# 03_-_Arduino_pcb_Schematic.net
KiCad netlist of a schematic drawn in Altium Designer
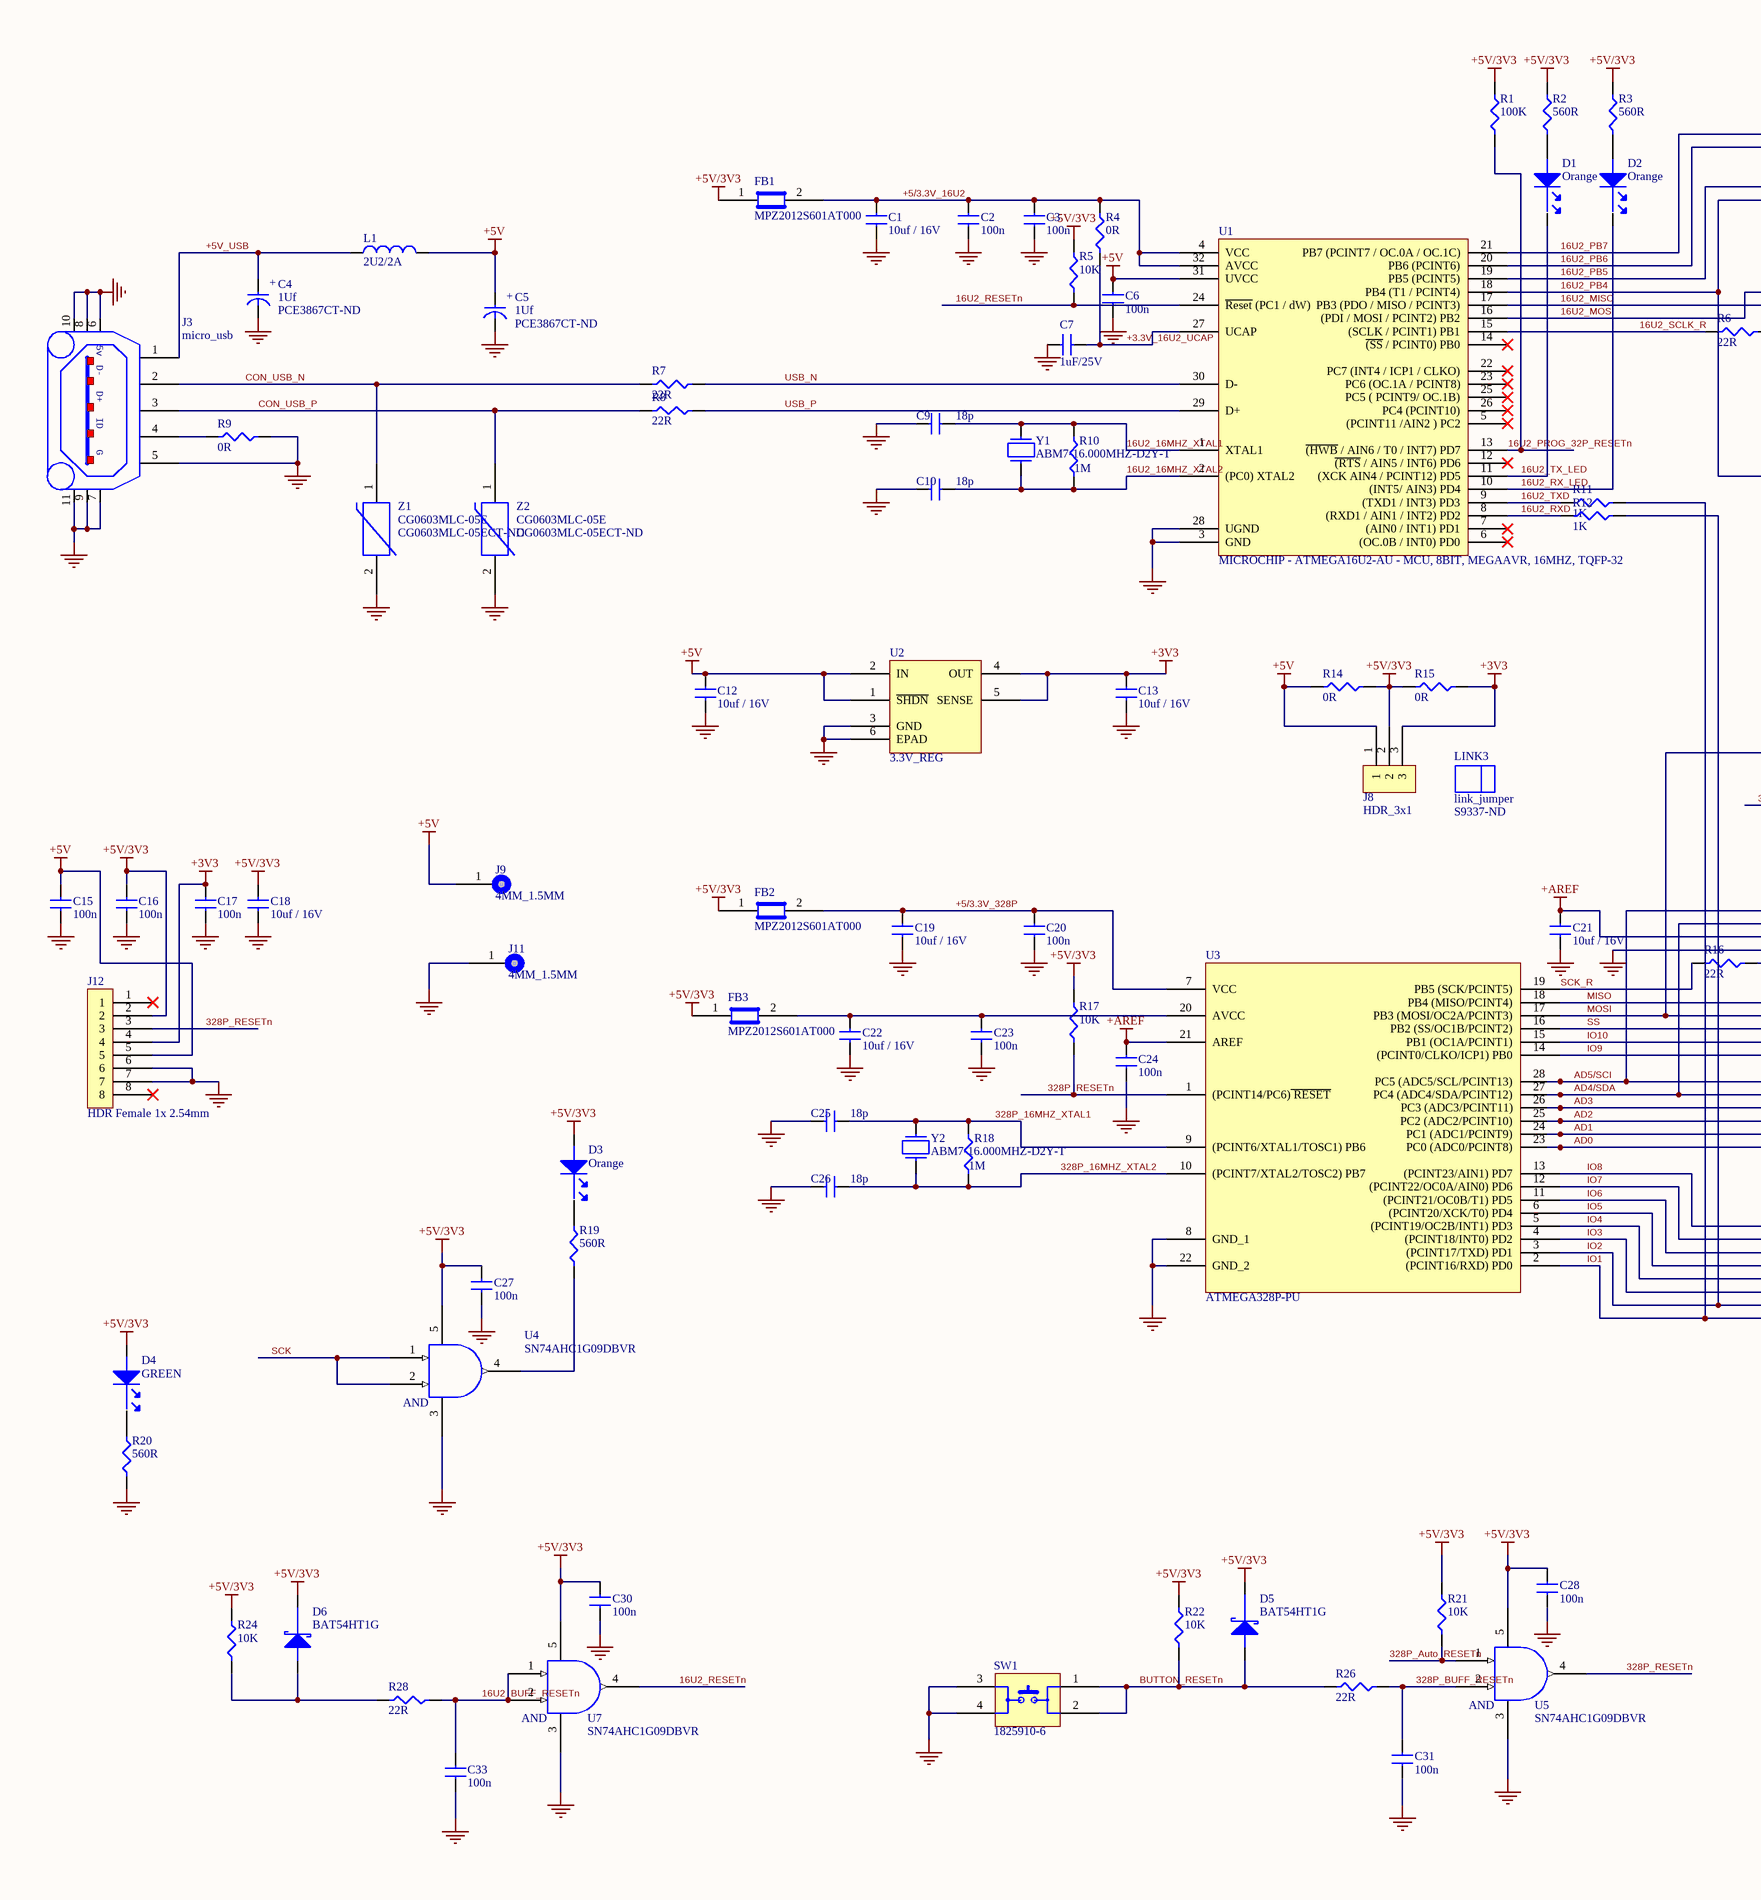
[diagram p0: [03] - Arduino_pcb_Schematic.SchDoc, left]
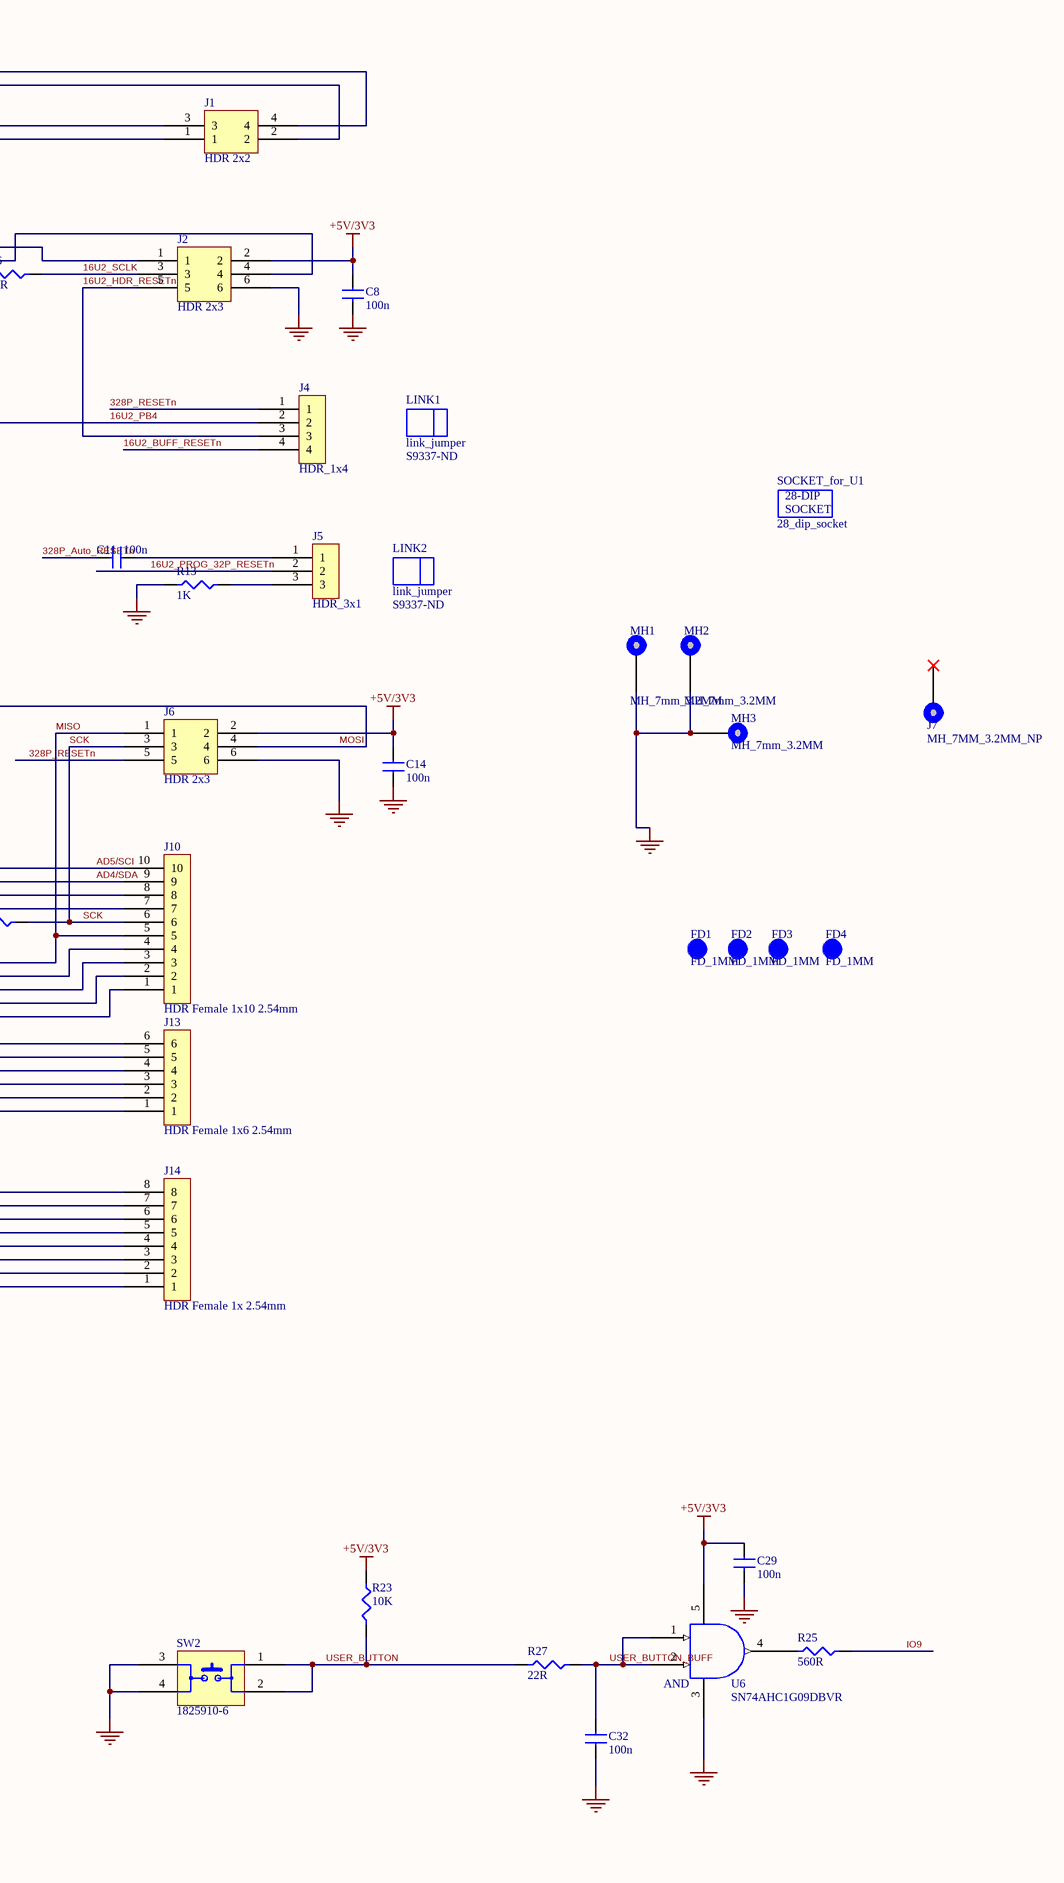
[diagram p1: [03] - Arduino_pcb_Schematic.SchDoc, right]

(export (version "E")
  (design (tool "Eeschema 10.0.6"))
  (components
    (comp (ref "C1")
      (value "10uf / 16V")
      (footprint "C0805_145")
      (fields
        (field (name "MANUFACTURER") "TDK")
        (field (name "MANUFACTURER PART NUMBER") "C2012X5R1C106K085AC")
        (field (name "TOLERANCE") "10%")
      )
      (libsource (lib "Arduino_pcb") (part "C2012X5R1C106K085AC"))
    )
    (comp (ref "C2")
      (value "100n")
      (footprint "C0805_95")
      (fields
        (field (name "MANUFACTURER") "TDK")
        (field (name "MANUFACTURER PART NUMBER") "C2012X7R1H104K085AA")
        (field (name "TOLERANCE") "10%")
      )
      (libsource (lib "Arduino_pcb") (part "C2012X7R1H104K085AA"))
    )
    (comp (ref "C3")
      (value "100n")
      (footprint "C0805_95")
      (fields
        (field (name "MANUFACTURER") "TDK")
        (field (name "MANUFACTURER PART NUMBER") "C2012X7R1H104K085AA")
        (field (name "TOLERANCE") "10%")
      )
      (libsource (lib "Arduino_pcb") (part "C2012X7R1H104K085AA"))
    )
    (comp (ref "C4")
      (value "1Uf")
      (footprint "C_ALIMUNUM_C_Size")
      (description "Cap Aluminum 100uF 10V 20% (5 X 5.4mm) SMD 50mA 1000 hr 85°C T/R")
      (fields
        (field (name "MANUFACTURER") "Panasonic")
        (field (name "MANUFACTURER PART NUMBER") "EEE-1AA101WR")
        (field (name "SUPPLIER PART NUMBER 1") "PCE3867CT-ND")
      )
      (libsource (lib "Arduino_pcb") (part "EEE-1AA101WR"))
    )
    (comp (ref "C5")
      (value "1Uf")
      (footprint "C_ALIMUNUM_C_Size")
      (description "Cap Aluminum 100uF 10V 20% (5 X 5.4mm) SMD 50mA 1000 hr 85°C T/R")
      (fields
        (field (name "MANUFACTURER") "Panasonic")
        (field (name "MANUFACTURER PART NUMBER") "EEE-1AA101WR")
        (field (name "SUPPLIER PART NUMBER 1") "PCE3867CT-ND")
      )
      (libsource (lib "Arduino_pcb") (part "EEE-1AA101WR"))
    )
    (comp (ref "C6")
      (value "100n")
      (footprint "C0805_95")
      (fields
        (field (name "MANUFACTURER") "TDK")
        (field (name "MANUFACTURER PART NUMBER") "C2012X7R1H104K085AA")
        (field (name "TOLERANCE") "10%")
      )
      (libsource (lib "Arduino_pcb") (part "C2012X7R1H104K085AA"))
    )
    (comp (ref "C7")
      (value "1uF/25V")
      (footprint "C0805_145")
      (fields
        (field (name "MANUFACTURER") "TDK")
        (field (name "MANUFACTURER PART NUMBER") "C2012X5R1E105K125AA")
        (field (name "TOLERANCE") "10%")
      )
      (libsource (lib "Arduino_pcb") (part "C2012X5R1E105K125AA"))
    )
    (comp (ref "C8")
      (value "100n")
      (footprint "C0805_95")
      (fields
        (field (name "MANUFACTURER") "TDK")
        (field (name "MANUFACTURER PART NUMBER") "C2012X7R1H104K085AA")
        (field (name "TOLERANCE") "10%")
      )
      (libsource (lib "Arduino_pcb") (part "C2012X7R1H104K085AA"))
    )
    (comp (ref "C9")
      (value "18p")
      (footprint "C0805_95")
      (description "CAP CER 18PF 50V C0G/NP0 0805")
      (fields
        (field (name "MANUFACTURER") "KEMET")
        (field (name "MANUFACTURER PART NUMBER") "C0805C180J5GACTU")
      )
      (libsource (lib "Arduino_pcb") (part "C0805C180J5GACTU"))
    )
    (comp (ref "C10")
      (value "18p")
      (footprint "C0805_95")
      (description "CAP CER 18PF 50V C0G/NP0 0805")
      (fields
        (field (name "MANUFACTURER") "KEMET")
        (field (name "MANUFACTURER PART NUMBER") "C0805C180J5GACTU")
      )
      (libsource (lib "Arduino_pcb") (part "C0805C180J5GACTU"))
    )
    (comp (ref "C11")
      (value "100n")
      (footprint "C0805_95")
      (fields
        (field (name "MANUFACTURER") "TDK")
        (field (name "MANUFACTURER PART NUMBER") "C2012X7R1H104K085AA")
        (field (name "TOLERANCE") "10%")
      )
      (libsource (lib "Arduino_pcb") (part "C2012X7R1H104K085AA"))
    )
    (comp (ref "C12")
      (value "10uf / 16V")
      (footprint "C0805_145")
      (fields
        (field (name "MANUFACTURER") "TDK")
        (field (name "MANUFACTURER PART NUMBER") "C2012X5R1C106K085AC")
        (field (name "TOLERANCE") "10%")
      )
      (libsource (lib "Arduino_pcb") (part "C2012X5R1C106K085AC"))
    )
    (comp (ref "C13")
      (value "10uf / 16V")
      (footprint "C0805_145")
      (fields
        (field (name "MANUFACTURER") "TDK")
        (field (name "MANUFACTURER PART NUMBER") "C2012X5R1C106K085AC")
        (field (name "TOLERANCE") "10%")
      )
      (libsource (lib "Arduino_pcb") (part "C2012X5R1C106K085AC"))
    )
    (comp (ref "C14")
      (value "100n")
      (footprint "C0805_95")
      (fields
        (field (name "MANUFACTURER") "TDK")
        (field (name "MANUFACTURER PART NUMBER") "C2012X7R1H104K085AA")
        (field (name "TOLERANCE") "10%")
      )
      (libsource (lib "Arduino_pcb") (part "C2012X7R1H104K085AA"))
    )
    (comp (ref "C15")
      (value "100n")
      (footprint "C0805_95")
      (fields
        (field (name "MANUFACTURER") "TDK")
        (field (name "MANUFACTURER PART NUMBER") "C2012X7R1H104K085AA")
        (field (name "TOLERANCE") "10%")
      )
      (libsource (lib "Arduino_pcb") (part "C2012X7R1H104K085AA"))
    )
    (comp (ref "C16")
      (value "100n")
      (footprint "C0805_95")
      (fields
        (field (name "MANUFACTURER") "TDK")
        (field (name "MANUFACTURER PART NUMBER") "C2012X7R1H104K085AA")
        (field (name "TOLERANCE") "10%")
      )
      (libsource (lib "Arduino_pcb") (part "C2012X7R1H104K085AA"))
    )
    (comp (ref "C17")
      (value "100n")
      (footprint "C0805_95")
      (fields
        (field (name "MANUFACTURER") "TDK")
        (field (name "MANUFACTURER PART NUMBER") "C2012X7R1H104K085AA")
        (field (name "TOLERANCE") "10%")
      )
      (libsource (lib "Arduino_pcb") (part "C2012X7R1H104K085AA"))
    )
    (comp (ref "C18")
      (value "10uf / 16V")
      (footprint "C0805_145")
      (fields
        (field (name "MANUFACTURER") "TDK")
        (field (name "MANUFACTURER PART NUMBER") "C2012X5R1C106K085AC")
        (field (name "TOLERANCE") "10%")
      )
      (libsource (lib "Arduino_pcb") (part "C2012X5R1C106K085AC"))
    )
    (comp (ref "C19")
      (value "10uf / 16V")
      (footprint "C0805_145")
      (fields
        (field (name "MANUFACTURER") "TDK")
        (field (name "MANUFACTURER PART NUMBER") "C2012X5R1C106K085AC")
        (field (name "TOLERANCE") "10%")
      )
      (libsource (lib "Arduino_pcb") (part "C2012X5R1C106K085AC"))
    )
    (comp (ref "C20")
      (value "100n")
      (footprint "C0805_95")
      (fields
        (field (name "MANUFACTURER") "TDK")
        (field (name "MANUFACTURER PART NUMBER") "C2012X7R1H104K085AA")
        (field (name "TOLERANCE") "10%")
      )
      (libsource (lib "Arduino_pcb") (part "C2012X7R1H104K085AA"))
    )
    (comp (ref "C21")
      (value "10uf / 16V")
      (footprint "C0805_145")
      (fields
        (field (name "MANUFACTURER") "TDK")
        (field (name "MANUFACTURER PART NUMBER") "C2012X5R1C106K085AC")
        (field (name "TOLERANCE") "10%")
      )
      (libsource (lib "Arduino_pcb") (part "C2012X5R1C106K085AC"))
    )
    (comp (ref "C22")
      (value "10uf / 16V")
      (footprint "C0805_145")
      (fields
        (field (name "MANUFACTURER") "TDK")
        (field (name "MANUFACTURER PART NUMBER") "C2012X5R1C106K085AC")
        (field (name "TOLERANCE") "10%")
      )
      (libsource (lib "Arduino_pcb") (part "C2012X5R1C106K085AC"))
    )
    (comp (ref "C23")
      (value "100n")
      (footprint "C0805_95")
      (fields
        (field (name "MANUFACTURER") "TDK")
        (field (name "MANUFACTURER PART NUMBER") "C2012X7R1H104K085AA")
        (field (name "TOLERANCE") "10%")
      )
      (libsource (lib "Arduino_pcb") (part "C2012X7R1H104K085AA"))
    )
    (comp (ref "C24")
      (value "100n")
      (footprint "C0805_95")
      (fields
        (field (name "MANUFACTURER") "TDK")
        (field (name "MANUFACTURER PART NUMBER") "C2012X7R1H104K085AA")
        (field (name "TOLERANCE") "10%")
      )
      (libsource (lib "Arduino_pcb") (part "C2012X7R1H104K085AA"))
    )
    (comp (ref "C25")
      (value "18p")
      (footprint "C0805_95")
      (description "CAP CER 18PF 50V C0G/NP0 0805")
      (fields
        (field (name "MANUFACTURER") "KEMET")
        (field (name "MANUFACTURER PART NUMBER") "C0805C180J5GACTU")
      )
      (libsource (lib "Arduino_pcb") (part "C0805C180J5GACTU"))
    )
    (comp (ref "C26")
      (value "18p")
      (footprint "C0805_95")
      (description "CAP CER 18PF 50V C0G/NP0 0805")
      (fields
        (field (name "MANUFACTURER") "KEMET")
        (field (name "MANUFACTURER PART NUMBER") "C0805C180J5GACTU")
      )
      (libsource (lib "Arduino_pcb") (part "C0805C180J5GACTU"))
    )
    (comp (ref "C27")
      (value "100n")
      (footprint "C0805_95")
      (fields
        (field (name "MANUFACTURER") "TDK")
        (field (name "MANUFACTURER PART NUMBER") "C2012X7R1H104K085AA")
        (field (name "TOLERANCE") "10%")
      )
      (libsource (lib "Arduino_pcb") (part "C2012X7R1H104K085AA"))
    )
    (comp (ref "C28")
      (value "100n")
      (footprint "C0805_95")
      (fields
        (field (name "MANUFACTURER") "TDK")
        (field (name "MANUFACTURER PART NUMBER") "C2012X7R1H104K085AA")
        (field (name "TOLERANCE") "10%")
      )
      (libsource (lib "Arduino_pcb") (part "C2012X7R1H104K085AA"))
    )
    (comp (ref "C29")
      (value "100n")
      (footprint "C0805_95")
      (fields
        (field (name "MANUFACTURER") "TDK")
        (field (name "MANUFACTURER PART NUMBER") "C2012X7R1H104K085AA")
        (field (name "TOLERANCE") "10%")
      )
      (libsource (lib "Arduino_pcb") (part "C2012X7R1H104K085AA"))
    )
    (comp (ref "C30")
      (value "100n")
      (footprint "C0805_95")
      (fields
        (field (name "MANUFACTURER") "TDK")
        (field (name "MANUFACTURER PART NUMBER") "C2012X7R1H104K085AA")
        (field (name "TOLERANCE") "10%")
      )
      (libsource (lib "Arduino_pcb") (part "C2012X7R1H104K085AA"))
    )
    (comp (ref "C31")
      (value "100n")
      (footprint "C0805_95")
      (fields
        (field (name "MANUFACTURER") "TDK")
        (field (name "MANUFACTURER PART NUMBER") "C2012X7R1H104K085AA")
        (field (name "TOLERANCE") "10%")
      )
      (libsource (lib "Arduino_pcb") (part "C2012X7R1H104K085AA"))
    )
    (comp (ref "C32")
      (value "100n")
      (footprint "C0805_95")
      (fields
        (field (name "MANUFACTURER") "TDK")
        (field (name "MANUFACTURER PART NUMBER") "C2012X7R1H104K085AA")
        (field (name "TOLERANCE") "10%")
      )
      (libsource (lib "Arduino_pcb") (part "C2012X7R1H104K085AA"))
    )
    (comp (ref "C33")
      (value "100n")
      (footprint "C0805_95")
      (fields
        (field (name "MANUFACTURER") "TDK")
        (field (name "MANUFACTURER PART NUMBER") "C2012X7R1H104K085AA")
        (field (name "TOLERANCE") "10%")
      )
      (libsource (lib "Arduino_pcb") (part "C2012X7R1H104K085AA"))
    )
    (comp (ref "D1")
      (value "Orange")
      (footprint "LED0603")
      (description "OSRAM - LO L29K-H2K1-24-Z - SMARTLED 0603 ORANGE")
      (fields
        (field (name "MANUFACTURER") "Osram Opto")
        (field (name "MANUFACTURER PART NUMBER") "LOL29K-H2K1-24-Z")
      )
      (libsource (lib "Arduino_pcb") (part "LOL29K-H2K1-24-Z"))
    )
    (comp (ref "D2")
      (value "Orange")
      (footprint "LED0603")
      (description "OSRAM - LO L29K-H2K1-24-Z - SMARTLED 0603 ORANGE")
      (fields
        (field (name "MANUFACTURER") "Osram Opto")
        (field (name "MANUFACTURER PART NUMBER") "LOL29K-H2K1-24-Z")
      )
      (libsource (lib "Arduino_pcb") (part "LOL29K-H2K1-24-Z"))
    )
    (comp (ref "D3")
      (value "Orange")
      (footprint "LED0603")
      (description "OSRAM - LO L29K-H2K1-24-Z - SMARTLED 0603 ORANGE")
      (fields
        (field (name "MANUFACTURER") "Osram Opto")
        (field (name "MANUFACTURER PART NUMBER") "LOL29K-H2K1-24-Z")
      )
      (libsource (lib "Arduino_pcb") (part "LOL29K-H2K1-24-Z"))
    )
    (comp (ref "D4")
      (value "GREEN")
      (footprint "LED0603")
      (description "LED Uni-Color Green 572nm 2-Pin Chip 0603(1608Metric) T/R")
      (fields
        (field (name "MANUFACTURER") "Osram Opto")
        (field (name "MANUFACTURER PART NUMBER") "LGL29K-G2J1-24-Z")
      )
      (libsource (lib "Arduino_pcb") (part "LGL29K-G2J1-24-Z"))
    )
    (comp (ref "D5")
      (value "BAT54HT1G")
      (footprint "BAT54HT1G")
      (description "Small Signal Schottky Diode, Single, 30 V, 200 mA, 800 mV, 600 mA, 150 C ;RoHS Compliant: Yes")
      (fields (field (name "MANUFACTURER") "ON Semiconductor / Fairchild"))
      (libsource (lib "Arduino_pcb") (part "BAT54HT1G"))
    )
    (comp (ref "D6")
      (value "BAT54HT1G")
      (footprint "BAT54HT1G")
      (description "Small Signal Schottky Diode, Single, 30 V, 200 mA, 800 mV, 600 mA, 150 C ;RoHS Compliant: Yes")
      (fields (field (name "MANUFACTURER") "ON Semiconductor / Fairchild"))
      (libsource (lib "Arduino_pcb") (part "BAT54HT1G"))
    )
    (comp (ref "FB1")
      (value "MPZ2012S601AT000")
      (footprint "FB0805_85")
      (description "FERRITE BEAD 600 OHM 0805 1LN")
      (fields (field (name "MANUFACTURER") "TDK"))
      (libsource (lib "Arduino_pcb") (part "MPZ2012S601AT000"))
    )
    (comp (ref "FB2")
      (value "MPZ2012S601AT000")
      (footprint "FB0805_85")
      (description "FERRITE BEAD 600 OHM 0805 1LN")
      (fields (field (name "MANUFACTURER") "TDK"))
      (libsource (lib "Arduino_pcb") (part "MPZ2012S601AT000"))
    )
    (comp (ref "FB3")
      (value "MPZ2012S601AT000")
      (footprint "FB0805_85")
      (description "FERRITE BEAD 600 OHM 0805 1LN")
      (fields (field (name "MANUFACTURER") "TDK"))
      (libsource (lib "Arduino_pcb") (part "MPZ2012S601AT000"))
    )
    (comp (ref "FD1")
      (value "FD_1MM")
      (footprint "FD_408120")
      (libsource (lib "Arduino_pcb") (part "FD_1MM"))
    )
    (comp (ref "FD2")
      (value "FD_1MM")
      (footprint "FD_408120")
      (libsource (lib "Arduino_pcb") (part "FD_1MM"))
    )
    (comp (ref "FD3")
      (value "FD_1MM")
      (footprint "FD_408120")
      (libsource (lib "Arduino_pcb") (part "FD_1MM"))
    )
    (comp (ref "FD4")
      (value "FD_1MM")
      (footprint "FD_408120")
      (libsource (lib "Arduino_pcb") (part "FD_1MM"))
    )
    (comp (ref "J1")
      (value "HDR 2x2")
      (footprint "HDR_2x2_2.54mm")
      (description "CONN HEADER VERT 4POS 2.54MM")
      (fields
        (field (name "MANUFACTURER") "Amphenol FCI")
        (field (name "MANUFACTURER PART NUMBER") "68602-204HLF")
      )
      (libsource (lib "Arduino_pcb") (part "68602-204HLF"))
    )
    (comp (ref "J2")
      (value "HDR 2x3")
      (footprint "HDR_3x2_2.54mm")
      (description "CONN HEADER 6POS .100 STR 30AU")
      (fields
        (field (name "MANUFACTURER") "Amphenol FCI")
        (field (name "MANUFACTURER PART NUMBER") "67997-106HLF")
      )
      (libsource (lib "Arduino_pcb") (part "67997-106HLF"))
    )
    (comp (ref "J3")
      (value "micro_usb")
      (footprint "MICRO_USB")
      (description "CONN USB MICRO B RECPT SMT R/A")
      (fields
        (field (name "MANUFACTURER") "Amphenol FCI")
        (field (name "MANUFACTURER PART NUMBER") "10118193-0001LF")
      )
      (libsource (lib "Arduino_pcb") (part "10118193-0001LF"))
    )
    (comp (ref "J4")
      (value "HDR_1x4")
      (footprint "HDR_Female_1x4_2.54mm")
      (description "CONN HEADER VERT 4POS 2.54MM")
      (fields
        (field (name "MANUFACTURER") "Amphenol FCI")
        (field (name "MANUFACTURER PART NUMBER") "68001-204HLF")
      )
      (libsource (lib "Arduino_pcb") (part "68001-204HLF"))
    )
    (comp (ref "J5")
      (value "HDR_3x1")
      (footprint "HDR_Female_1x3_2.54mm")
      (description "Conn Unshrouded Header HDR 3 POS 2.54mm Solder ST Thru-Hole Bulk")
      (fields
        (field (name "MANUFACTURER") "Amphenol FCI")
        (field (name "MANUFACTURER PART NUMBER") "68000-103HLF")
      )
      (libsource (lib "Arduino_pcb") (part "68000-103HLF"))
    )
    (comp (ref "J6")
      (value "HDR 2x3")
      (footprint "HDR_3x2_2.54mm")
      (description "CONN HEADER 6POS .100 STR 30AU")
      (fields
        (field (name "MANUFACTURER") "Amphenol FCI")
        (field (name "MANUFACTURER PART NUMBER") "67997-106HLF")
      )
      (libsource (lib "Arduino_pcb") (part "67997-106HLF"))
    )
    (comp (ref "J7")
      (value "MH_7MM_3.2MM_NP")
      (footprint "MH_7mm_3.2MM_NP")
      (libsource (lib "Arduino_pcb") (part "MH_7MM_3.2MM_NP"))
    )
    (comp (ref "J8")
      (value "HDR_3x1")
      (footprint "HDR_Female_1x3_2.54mm")
      (description "Conn Unshrouded Header HDR 3 POS 2.54mm Solder ST Thru-Hole Bulk")
      (fields
        (field (name "MANUFACTURER") "Amphenol FCI")
        (field (name "MANUFACTURER PART NUMBER") "68000-103HLF")
      )
      (libsource (lib "") (part "68000-103HLF_1"))
    )
    (comp (ref "J9")
      (value "4MM_1.5MM")
      (footprint "PAD_WITH_HOLE_4mm_1.5mm")
      (description "PAD_WITH_HOLE_4MM_1.5MM")
      (libsource (lib "Arduino_pcb") (part "PAD_WITH_HOLE_4mm_1.5mm"))
    )
    (comp (ref "J10")
      (value "HDR Female 1x10 2.54mm")
      (footprint "HDR_Female_1x10_2.54mm")
      (fields (field (name "MANUFACTURER") "Harwin") (field (name "MANUFACTURER PART NUMBER") "M20-7821046"))
      (libsource (lib "Arduino_pcb") (part "M20-7821046"))
    )
    (comp (ref "J11")
      (value "4MM_1.5MM")
      (footprint "PAD_WITH_HOLE_4mm_1.5mm")
      (description "PAD_WITH_HOLE_4MM_1.5MM")
      (libsource (lib "Arduino_pcb") (part "PAD_WITH_HOLE_4mm_1.5mm"))
    )
    (comp (ref "J12")
      (value "HDR Female 1x 2.54mm")
      (footprint "HDR_Female_1x8_2.54mm")
      (description "2.54mm (0.1\") Pitch SIL Vertical PC Tail Socket Assembly, selective gold + tin, 8 contacts")
      (fields (field (name "MANUFACTURER") "Harwin") (field (name "MANUFACTURER PART NUMBER") "M20-7820842"))
      (libsource (lib "Arduino_pcb") (part "M20-7820842"))
    )
    (comp (ref "J13")
      (value "HDR Female 1x6 2.54mm")
      (footprint "HDR_Female_1x 6_2.54mm")
      (description "06-WAY SIL VERT SOCKET L/FREE")
      (fields (field (name "MANUFACTURER") "Harwin") (field (name "MANUFACTURER PART NUMBER") "M20-7820646"))
      (libsource (lib "Arduino_pcb") (part "M20-7820646"))
    )
    (comp (ref "J14")
      (value "HDR Female 1x 2.54mm")
      (footprint "HDR_Female_1x8_2.54mm")
      (description "2.54mm (0.1\") Pitch SIL Vertical PC Tail Socket Assembly, selective gold + tin, 8 contacts")
      (fields (field (name "MANUFACTURER") "Harwin") (field (name "MANUFACTURER PART NUMBER") "M20-7820842"))
      (libsource (lib "") (part "M20-7820842_1"))
    )
    (comp (ref "L1")
      (value "2U2/2A")
      (footprint "C2120_L")
      (description "FIXED IND 2.2UH 2A 80 MOHM SMD")
      (fields
        (field (name "MANUFACTURER") "KEMET")
        (field (name "MANUFACTURER PART NUMBER") "L1210R2R2MDWIT")
      )
      (libsource (lib "Arduino_pcb") (part "L1210R2R2MDWIT"))
    )
    (comp (ref "LINK1")
      (value "link_jumper")
      (description "CONN JUMPER SHORTING .100\" GOLD")
      (fields
        (field (name "MANUFACTURER") "Sullins")
        (field (name "MANUFACTURER PART NUMBER") "QPC02SXGN-RC")
        (field (name "SUPPLIER PART NUMBER 1") "S9337-ND")
      )
      (libsource (lib "Arduino_pcb") (part "QPC02SXGN-RC"))
    )
    (comp (ref "LINK2")
      (value "link_jumper")
      (description "CONN JUMPER SHORTING .100\" GOLD")
      (fields
        (field (name "MANUFACTURER") "Sullins")
        (field (name "MANUFACTURER PART NUMBER") "QPC02SXGN-RC")
        (field (name "SUPPLIER PART NUMBER 1") "S9337-ND")
      )
      (libsource (lib "Arduino_pcb") (part "QPC02SXGN-RC"))
    )
    (comp (ref "LINK3")
      (value "link_jumper")
      (description "CONN JUMPER SHORTING .100\" GOLD")
      (fields
        (field (name "MANUFACTURER") "Sullins")
        (field (name "MANUFACTURER PART NUMBER") "QPC02SXGN-RC")
        (field (name "SUPPLIER PART NUMBER 1") "S9337-ND")
      )
      (libsource (lib "Arduino_pcb") (part "QPC02SXGN-RC"))
    )
    (comp (ref "MH1")
      (value "MH_7mm_3.2MM")
      (footprint "MH_7mm_3.2MM")
      (libsource (lib "Arduino_pcb") (part "MH_7mm_3.2MM"))
    )
    (comp (ref "MH2")
      (value "MH_7mm_3.2MM")
      (footprint "MH_7mm_3.2MM")
      (libsource (lib "Arduino_pcb") (part "MH_7mm_3.2MM"))
    )
    (comp (ref "MH3")
      (value "MH_7mm_3.2MM")
      (footprint "MH_7mm_3.2MM")
      (libsource (lib "Arduino_pcb") (part "MH_7mm_3.2MM"))
    )
    (comp (ref "R1")
      (value "100K")
      (footprint "R0805")
      (description "YAGEO         RC0805FR-07100KL            RES, THICK FILM, 100K, 1%, 0.125W, 0805, REEL")
      (fields
        (field (name "MANUFACTURER") "Yageo")
        (field (name "MANUFACTURER PART NUMBER") "RC0805FR-07100KL")
      )
      (libsource (lib "Arduino_pcb") (part "RC0805FR-07100KL"))
    )
    (comp (ref "R2")
      (value "560R")
      (footprint "R0805")
      (description "Surface Mount Thick Film Resistor, RC Series, 560 ohm, 125 mW, - 1%, 150 V, 0805 [2012 Metric]")
      (fields
        (field (name "MANUFACTURER") "Yageo")
        (field (name "MANUFACTURER PART NUMBER") "RC0805FR-07560RL")
      )
      (libsource (lib "Arduino_pcb") (part "RC0805FR-07560RL"))
    )
    (comp (ref "R3")
      (value "560R")
      (footprint "R0805")
      (description "Surface Mount Thick Film Resistor, RC Series, 560 ohm, 125 mW, - 1%, 150 V, 0805 [2012 Metric]")
      (fields
        (field (name "MANUFACTURER") "Yageo")
        (field (name "MANUFACTURER PART NUMBER") "RC0805FR-07560RL")
      )
      (libsource (lib "Arduino_pcb") (part "RC0805FR-07560RL"))
    )
    (comp (ref "R4")
      (value "0R")
      (footprint "R0805")
      (description "Surface Mount Thick Film Resistor, RC Series, 125 mW, - 5%, 150 V, 0805 [2012 Metric]")
      (fields
        (field (name "MANUFACTURER") "Yageo")
        (field (name "MANUFACTURER PART NUMBER") "RC0805JR-070RL")
      )
      (libsource (lib "Arduino_pcb") (part "RC0805JR-070RL"))
    )
    (comp (ref "R5")
      (value "10K")
      (footprint "R0805")
      (description "RES SMD 10K OHM 1% 1/8W 0805")
      (fields
        (field (name "MANUFACTURER") "Yageo")
        (field (name "MANUFACTURER PART NUMBER") "RC0805FR-0710KL")
      )
      (libsource (lib "Arduino_pcb") (part "RC0805FR-0710KL"))
    )
    (comp (ref "R6")
      (value "22R")
      (footprint "R0805")
      (description "RES SMD 22 OHM 1% 1/8W 0805")
      (fields
        (field (name "MANUFACTURER") "Yageo")
        (field (name "MANUFACTURER PART NUMBER") "RC0805FR-0722RL")
      )
      (libsource (lib "Arduino_pcb") (part "RC0805FR-0722RL"))
    )
    (comp (ref "R7")
      (value "22R")
      (footprint "R0805")
      (description "RES SMD 22 OHM 1% 1/8W 0805")
      (fields
        (field (name "MANUFACTURER") "Yageo")
        (field (name "MANUFACTURER PART NUMBER") "RC0805FR-0722RL")
      )
      (libsource (lib "Arduino_pcb") (part "RC0805FR-0722RL"))
    )
    (comp (ref "R8")
      (value "22R")
      (footprint "R0805")
      (description "RES SMD 22 OHM 1% 1/8W 0805")
      (fields
        (field (name "MANUFACTURER") "Yageo")
        (field (name "MANUFACTURER PART NUMBER") "RC0805FR-0722RL")
      )
      (libsource (lib "Arduino_pcb") (part "RC0805FR-0722RL"))
    )
    (comp (ref "R9")
      (value "0R")
      (footprint "R0805")
      (description "Surface Mount Thick Film Resistor, RC Series, 125 mW, - 5%, 150 V, 0805 [2012 Metric]")
      (fields
        (field (name "MANUFACTURER") "Yageo")
        (field (name "MANUFACTURER PART NUMBER") "RC0805JR-070RL")
      )
      (libsource (lib "Arduino_pcb") (part "RC0805JR-070RL"))
    )
    (comp (ref "R10")
      (value "1M")
      (footprint "R0805")
      (description "RES SMD 1M OHM 1% 1/8W 0805")
      (fields
        (field (name "MANUFACTURER") "Yageo")
        (field (name "MANUFACTURER PART NUMBER") "RC0805FR-071ML")
      )
      (libsource (lib "Arduino_pcb") (part "RC0805FR-071ML"))
    )
    (comp (ref "R11")
      (value "1K")
      (footprint "R0805")
      (fields
        (field (name "MANUFACTURER") "Yageo")
        (field (name "MANUFACTURER PART NUMBER") "RC0805FR-071KL")
        (field (name "TOLERANCE") "1%")
      )
      (libsource (lib "Arduino_pcb") (part "RC0805FR-071KL"))
    )
    (comp (ref "R12")
      (value "1K")
      (footprint "R0805")
      (fields
        (field (name "MANUFACTURER") "Yageo")
        (field (name "MANUFACTURER PART NUMBER") "RC0805FR-071KL")
        (field (name "TOLERANCE") "1%")
      )
      (libsource (lib "Arduino_pcb") (part "RC0805FR-071KL"))
    )
    (comp (ref "R13")
      (value "1K")
      (footprint "R0805")
      (fields
        (field (name "MANUFACTURER") "Yageo")
        (field (name "MANUFACTURER PART NUMBER") "RC0805FR-071KL")
        (field (name "TOLERANCE") "1%")
      )
      (libsource (lib "Arduino_pcb") (part "RC0805FR-071KL"))
    )
    (comp (ref "R14")
      (value "0R")
      (footprint "R0805")
      (description "Surface Mount Thick Film Resistor, RC Series, 125 mW, - 5%, 150 V, 0805 [2012 Metric]")
      (fields
        (field (name "MANUFACTURER") "Yageo")
        (field (name "MANUFACTURER PART NUMBER") "RC0805JR-070RL")
      )
      (libsource (lib "Arduino_pcb") (part "RC0805JR-070RL"))
    )
    (comp (ref "R15")
      (value "0R")
      (footprint "R0805")
      (description "Surface Mount Thick Film Resistor, RC Series, 125 mW, - 5%, 150 V, 0805 [2012 Metric]")
      (fields
        (field (name "MANUFACTURER") "Yageo")
        (field (name "MANUFACTURER PART NUMBER") "RC0805JR-070RL")
      )
      (libsource (lib "Arduino_pcb") (part "RC0805JR-070RL"))
    )
    (comp (ref "R16")
      (value "22R")
      (footprint "R0805")
      (description "RES SMD 22 OHM 1% 1/8W 0805")
      (fields
        (field (name "MANUFACTURER") "Yageo")
        (field (name "MANUFACTURER PART NUMBER") "RC0805FR-0722RL")
      )
      (libsource (lib "Arduino_pcb") (part "RC0805FR-0722RL"))
    )
    (comp (ref "R17")
      (value "10K")
      (footprint "R0805")
      (description "RES SMD 10K OHM 1% 1/8W 0805")
      (fields
        (field (name "MANUFACTURER") "Yageo")
        (field (name "MANUFACTURER PART NUMBER") "RC0805FR-0710KL")
      )
      (libsource (lib "Arduino_pcb") (part "RC0805FR-0710KL"))
    )
    (comp (ref "R18")
      (value "1M")
      (footprint "R0805")
      (description "RES SMD 1M OHM 1% 1/8W 0805")
      (fields
        (field (name "MANUFACTURER") "Yageo")
        (field (name "MANUFACTURER PART NUMBER") "RC0805FR-071ML")
      )
      (libsource (lib "Arduino_pcb") (part "RC0805FR-071ML"))
    )
    (comp (ref "R19")
      (value "560R")
      (footprint "R0805")
      (description "Surface Mount Thick Film Resistor, RC Series, 560 ohm, 125 mW, - 1%, 150 V, 0805 [2012 Metric]")
      (fields
        (field (name "MANUFACTURER") "Yageo")
        (field (name "MANUFACTURER PART NUMBER") "RC0805FR-07560RL")
      )
      (libsource (lib "Arduino_pcb") (part "RC0805FR-07560RL"))
    )
    (comp (ref "R20")
      (value "560R")
      (footprint "R0805")
      (description "Surface Mount Thick Film Resistor, RC Series, 560 ohm, 125 mW, - 1%, 150 V, 0805 [2012 Metric]")
      (fields
        (field (name "MANUFACTURER") "Yageo")
        (field (name "MANUFACTURER PART NUMBER") "RC0805FR-07560RL")
      )
      (libsource (lib "Arduino_pcb") (part "RC0805FR-07560RL"))
    )
    (comp (ref "R21")
      (value "10K")
      (footprint "R0805")
      (description "RES SMD 10K OHM 1% 1/8W 0805")
      (fields
        (field (name "MANUFACTURER") "Yageo")
        (field (name "MANUFACTURER PART NUMBER") "RC0805FR-0710KL")
      )
      (libsource (lib "Arduino_pcb") (part "RC0805FR-0710KL"))
    )
    (comp (ref "R22")
      (value "10K")
      (footprint "R0805")
      (description "RES SMD 10K OHM 1% 1/8W 0805")
      (fields
        (field (name "MANUFACTURER") "Yageo")
        (field (name "MANUFACTURER PART NUMBER") "RC0805FR-0710KL")
      )
      (libsource (lib "Arduino_pcb") (part "RC0805FR-0710KL"))
    )
    (comp (ref "R23")
      (value "10K")
      (footprint "R0805")
      (description "RES SMD 10K OHM 1% 1/8W 0805")
      (fields
        (field (name "MANUFACTURER") "Yageo")
        (field (name "MANUFACTURER PART NUMBER") "RC0805FR-0710KL")
      )
      (libsource (lib "Arduino_pcb") (part "RC0805FR-0710KL"))
    )
    (comp (ref "R24")
      (value "10K")
      (footprint "R0805")
      (description "RES SMD 10K OHM 1% 1/8W 0805")
      (fields
        (field (name "MANUFACTURER") "Yageo")
        (field (name "MANUFACTURER PART NUMBER") "RC0805FR-0710KL")
      )
      (libsource (lib "Arduino_pcb") (part "RC0805FR-0710KL"))
    )
    (comp (ref "R25")
      (value "560R")
      (footprint "R0805")
      (description "Surface Mount Thick Film Resistor, RC Series, 560 ohm, 125 mW, - 1%, 150 V, 0805 [2012 Metric]")
      (fields
        (field (name "MANUFACTURER") "Yageo")
        (field (name "MANUFACTURER PART NUMBER") "RC0805FR-07560RL")
      )
      (libsource (lib "Arduino_pcb") (part "RC0805FR-07560RL"))
    )
    (comp (ref "R26")
      (value "22R")
      (footprint "R0805")
      (description "RES SMD 22 OHM 1% 1/8W 0805")
      (fields
        (field (name "MANUFACTURER") "Yageo")
        (field (name "MANUFACTURER PART NUMBER") "RC0805FR-0722RL")
      )
      (libsource (lib "Arduino_pcb") (part "RC0805FR-0722RL"))
    )
    (comp (ref "R27")
      (value "22R")
      (footprint "R0805")
      (description "RES SMD 22 OHM 1% 1/8W 0805")
      (fields
        (field (name "MANUFACTURER") "Yageo")
        (field (name "MANUFACTURER PART NUMBER") "RC0805FR-0722RL")
      )
      (libsource (lib "Arduino_pcb") (part "RC0805FR-0722RL"))
    )
    (comp (ref "R28")
      (value "22R")
      (footprint "R0805")
      (description "RES SMD 22 OHM 1% 1/8W 0805")
      (fields
        (field (name "MANUFACTURER") "Yageo")
        (field (name "MANUFACTURER PART NUMBER") "RC0805FR-0722RL")
      )
      (libsource (lib "Arduino_pcb") (part "RC0805FR-0722RL"))
    )
    (comp (ref "SOCKET_for_U1")
      (value "28_dip_socket")
      (footprint "DIP_28_Socket")
      (description "CONN IC DIP SOCKET 28POS TIN")
      (fields (field (name "MANUFACTURER") "3M") (field (name "MANUFACTURER PART NUMBER") "4828-3004-CP"))
      (libsource (lib "Arduino_pcb") (part "4828-3004-CP"))
    )
    (comp (ref "SW1")
      (value "1825910-6")
      (footprint "SW_1825910-6")
      (description "SWITCH TACTILE SPST-NO 0.05A 24V")
      (fields (field (name "MANUFACTURER") "TE Connectivity Alcoswitch"))
      (libsource (lib "Arduino_pcb") (part "1825910-6"))
    )
    (comp (ref "SW2")
      (value "1825910-6")
      (footprint "SW_1825910-6")
      (description "SWITCH TACTILE SPST-NO 0.05A 24V")
      (fields (field (name "MANUFACTURER") "TE Connectivity Alcoswitch"))
      (libsource (lib "Arduino_pcb") (part "1825910-6"))
    )
    (comp (ref "U1")
      (value "MICROCHIP - ATMEGA16U2-AU - MCU, 8BIT, MEGAAVR, 16MHZ, TQFP-32")
      (footprint "TQFB32")
      (fields
        (field (name "MANUFACTURER") "Microchip / Atmel")
        (field (name "MANUFACTURER PART NUMBER") "ATMEGA16U2-AU")
      )
      (libsource (lib "Arduino_pcb") (part "ATMEGA16U2-AU"))
    )
    (comp (ref "U2")
      (value "3.3V_REG")
      (footprint "DCQR_PDSO_3.3")
      (description "IC REG LINEAR 3.3V 1.5A SOT223-6")
      (fields
        (field (name "MANUFACTURER") "Texas Instruments")
        (field (name "MANUFACTURER PART NUMBER") "TL1963A-33DCQR")
      )
      (libsource (lib "Arduino_pcb") (part "TL1963A-33DCQR"))
    )
    (comp (ref "U3")
      (value "ATMEGA328P-PU")
      (footprint "28_DIP_7.62mm")
      (description "ATMEGA328P-PU; 8 bit Microcontroller AVR 20MHz 1; 32kb Flash; 2kb RAM; I2C SPI 2")
      (fields (field (name "MANUFACTURER") "Microchip / Atmel"))
      (libsource (lib "Arduino_pcb") (part "ATMEGA328P-PU"))
    )
    (comp (ref "U4")
      (value "SN74AHC1G09DBVR")
      (footprint "DBV_SOT_23_5")
      (description "TEXAS INSTRUMENTS - SN74AHC1G09DBVR - AND Gate, 74AHC1G09, 2 Input, 2 V to 5.5 V, SOT-23-5")
      (fields (field (name "MANUFACTURER") "Texas Instruments"))
      (libsource (lib "Arduino_pcb") (part "SN74AHC1G09DBVR"))
    )
    (comp (ref "U5")
      (value "SN74AHC1G09DBVR")
      (footprint "DBV_SOT_23_5")
      (description "TEXAS INSTRUMENTS - SN74AHC1G09DBVR - AND Gate, 74AHC1G09, 2 Input, 2 V to 5.5 V, SOT-23-5")
      (fields (field (name "MANUFACTURER") "Texas Instruments"))
      (libsource (lib "Arduino_pcb") (part "SN74AHC1G09DBVR"))
    )
    (comp (ref "U6")
      (value "SN74AHC1G09DBVR")
      (footprint "DBV_SOT_23_5")
      (description "TEXAS INSTRUMENTS - SN74AHC1G09DBVR - AND Gate, 74AHC1G09, 2 Input, 2 V to 5.5 V, SOT-23-5")
      (fields (field (name "MANUFACTURER") "Texas Instruments"))
      (libsource (lib "Arduino_pcb") (part "SN74AHC1G09DBVR"))
    )
    (comp (ref "U7")
      (value "SN74AHC1G09DBVR")
      (footprint "DBV_SOT_23_5")
      (description "TEXAS INSTRUMENTS - SN74AHC1G09DBVR - AND Gate, 74AHC1G09, 2 Input, 2 V to 5.5 V, SOT-23-5")
      (fields (field (name "MANUFACTURER") "Texas Instruments"))
      (libsource (lib "Arduino_pcb") (part "SN74AHC1G09DBVR"))
    )
    (comp (ref "Y1")
      (value "ABM7-16.000MHZ-D2Y-T")
      (footprint "ABM7_BIG")
      (description "CRYSTAL 16.0000MHZ 18PF SMD")
      (fields (field (name "MANUFACTURER") "Abracon") (field (name "TOLERANCE") "20ppm"))
      (libsource (lib "Arduino_pcb") (part "ABM7-16.000MHZ-D2Y-T"))
    )
    (comp (ref "Y2")
      (value "ABM7-16.000MHZ-D2Y-T")
      (footprint "ABM7_BIG")
      (description "CRYSTAL 16.0000MHZ 18PF SMD")
      (fields (field (name "MANUFACTURER") "Abracon") (field (name "TOLERANCE") "20ppm"))
      (libsource (lib "Arduino_pcb") (part "ABM7-16.000MHZ-D2Y-T"))
    )
    (comp (ref "Z1")
      (value "CG0603MLC-05E")
      (footprint "R0603")
      (description "VARISTOR 0603")
      (fields
        (field (name "MANUFACTURER") "Bourns")
        (field (name "VOLTAGE") "5V")
        (field (name "SUPPLIER PART NUMBER 1") "CG0603MLC-05ECT-ND")
      )
      (libsource (lib "Arduino_pcb") (part "CG0603MLC-05E"))
    )
    (comp (ref "Z2")
      (value "CG0603MLC-05E")
      (footprint "R0603")
      (description "VARISTOR 0603")
      (fields
        (field (name "MANUFACTURER") "Bourns")
        (field (name "VOLTAGE") "5V")
        (field (name "SUPPLIER PART NUMBER 1") "CG0603MLC-05ECT-ND")
      )
      (libsource (lib "Arduino_pcb") (part "CG0603MLC-05E"))
    )
  )
  (nets
    (net (code "1") (name "+3V3") (class "Default")
      (node (ref "C13") (pin "2") (pinfunction "2_2") (pintype "passive"))
      (node (ref "C17") (pin "2") (pinfunction "2_2") (pintype "passive"))
      (node (ref "J12") (pin "4") (pinfunction "4_4") (pintype "passive"))
      (node (ref "J8") (pin "3") (pinfunction "3_3") (pintype "passive"))
      (node (ref "R15") (pin "2") (pinfunction "2_2") (pintype "passive"))
      (node (ref "U2") (pin "4") (pinfunction "OUT_4") (pintype "passive"))
      (node (ref "U2") (pin "5") (pinfunction "SENSE_5") (pintype "passive"))
    )
    (net (code "2") (name "+5V") (class "Default")
      (node (ref "C12") (pin "2") (pinfunction "2_2") (pintype "passive"))
      (node (ref "C15") (pin "2") (pinfunction "2_2") (pintype "passive"))
      (node (ref "C5") (pin "1") (pinfunction "1_1") (pintype "passive"))
      (node (ref "C6") (pin "2") (pinfunction "2_2") (pintype "passive"))
      (node (ref "J12") (pin "5") (pinfunction "5_5") (pintype "passive"))
      (node (ref "J8") (pin "1") (pinfunction "1_1") (pintype "passive"))
      (node (ref "J9") (pin "1") (pintype "passive"))
      (node (ref "L1") (pin "2") (pinfunction "2_2") (pintype "passive"))
      (node (ref "R14") (pin "1") (pinfunction "1_1") (pintype "passive"))
      (node (ref "U1") (pin "31") (pinfunction "UVCC_31") (pintype "passive"))
      (node (ref "U2") (pin "1") (pinfunction "~{SHDN}_1") (pintype "passive"))
      (node (ref "U2") (pin "2") (pinfunction "IN_2") (pintype "passive"))
    )
    (net (code "3") (name "+5V{slash}3V3") (class "Default")
      (node (ref "C14") (pin "2") (pinfunction "2_2") (pintype "passive"))
      (node (ref "C16") (pin "2") (pinfunction "2_2") (pintype "passive"))
      (node (ref "C18") (pin "2") (pinfunction "2_2") (pintype "passive"))
      (node (ref "C27") (pin "2") (pinfunction "2_2") (pintype "passive"))
      (node (ref "C28") (pin "2") (pinfunction "2_2") (pintype "passive"))
      (node (ref "C29") (pin "2") (pinfunction "2_2") (pintype "passive"))
      (node (ref "C30") (pin "2") (pinfunction "2_2") (pintype "passive"))
      (node (ref "C8") (pin "2") (pinfunction "2_2") (pintype "passive"))
      (node (ref "D3") (pin "2") (pinfunction "Anode_2") (pintype "passive"))
      (node (ref "D4") (pin "2") (pinfunction "Anode_2") (pintype "passive"))
      (node (ref "D5") (pin "1") (pinfunction "Cathode_1") (pintype "passive"))
      (node (ref "D6") (pin "1") (pinfunction "Cathode_1") (pintype "passive"))
      (node (ref "FB1") (pin "1") (pinfunction "1_1") (pintype "passive"))
      (node (ref "FB2") (pin "1") (pinfunction "1_1") (pintype "passive"))
      (node (ref "FB3") (pin "1") (pinfunction "1_1") (pintype "passive"))
      (node (ref "J12") (pin "2") (pinfunction "2_2") (pintype "passive"))
      (node (ref "J2") (pin "2") (pinfunction "2_2") (pintype "passive"))
      (node (ref "J6") (pin "2") (pinfunction "2_2") (pintype "passive"))
      (node (ref "J8") (pin "2") (pinfunction "2_2") (pintype "passive"))
      (node (ref "R1") (pin "2") (pinfunction "2_2") (pintype "passive"))
      (node (ref "R14") (pin "2") (pinfunction "2_2") (pintype "passive"))
      (node (ref "R15") (pin "1") (pinfunction "1_1") (pintype "passive"))
      (node (ref "R17") (pin "2") (pinfunction "2_2") (pintype "passive"))
      (node (ref "R2") (pin "2") (pinfunction "2_2") (pintype "passive"))
      (node (ref "R21") (pin "2") (pinfunction "2_2") (pintype "passive"))
      (node (ref "R22") (pin "2") (pinfunction "2_2") (pintype "passive"))
      (node (ref "R23") (pin "2") (pinfunction "2_2") (pintype "passive"))
      (node (ref "R24") (pin "2") (pinfunction "2_2") (pintype "passive"))
      (node (ref "R3") (pin "2") (pinfunction "2_2") (pintype "passive"))
      (node (ref "R5") (pin "1") (pinfunction "1_1") (pintype "passive"))
      (node (ref "U4") (pin "5") (pinfunction "5_5") (pintype "passive"))
      (node (ref "U5") (pin "5") (pinfunction "5_5") (pintype "passive"))
      (node (ref "U6") (pin "5") (pinfunction "5_5") (pintype "passive"))
      (node (ref "U7") (pin "5") (pinfunction "5_5") (pintype "passive"))
    )
    (net (code "4") (name "+AREF") (class "Default")
      (node (ref "C21") (pin "2") (pinfunction "2_2") (pintype "passive"))
      (node (ref "C24") (pin "2") (pinfunction "2_2") (pintype "passive"))
      (node (ref "J10") (pin "8") (pinfunction "8_8") (pintype "passive"))
      (node (ref "U3") (pin "21") (pinfunction "AREF_21") (pintype "passive"))
    )
    (net (code "5") (name "/+3.3V_16U2_UCAP") (class "Default")
      (node (ref "C7") (pin "2") (pinfunction "2_2") (pintype "passive"))
      (node (ref "R4") (pin "1") (pinfunction "1_1") (pintype "passive"))
      (node (ref "U1") (pin "27") (pinfunction "UCAP_27") (pintype "passive"))
    )
    (net (code "6") (name "/+5V_USB") (class "Default")
      (node (ref "C4") (pin "1") (pinfunction "1_1") (pintype "passive"))
      (node (ref "J3") (pin "1") (pinfunction "1_1") (pintype "passive"))
      (node (ref "L1") (pin "1") (pinfunction "1_1") (pintype "passive"))
    )
    (net (code "7") (name "/+5{slash}3.3V_16U2") (class "Default")
      (node (ref "C1") (pin "2") (pinfunction "2_2") (pintype "passive"))
      (node (ref "C2") (pin "2") (pinfunction "2_2") (pintype "passive"))
      (node (ref "C3") (pin "2") (pinfunction "2_2") (pintype "passive"))
      (node (ref "FB1") (pin "2") (pinfunction "2_2") (pintype "passive"))
      (node (ref "R4") (pin "2") (pinfunction "2_2") (pintype "passive"))
      (node (ref "U1") (pin "32") (pinfunction "AVCC_32") (pintype "passive"))
      (node (ref "U1") (pin "4") (pinfunction "VCC_4") (pintype "passive"))
    )
    (net (code "8") (name "/+5{slash}3.3V_328P") (class "Default")
      (node (ref "C19") (pin "2") (pinfunction "2_2") (pintype "passive"))
      (node (ref "C20") (pin "2") (pinfunction "2_2") (pintype "passive"))
      (node (ref "FB2") (pin "2") (pinfunction "2_2") (pintype "passive"))
      (node (ref "U3") (pin "7") (pinfunction "VCC_7") (pintype "passive"))
    )
    (net (code "9") (name "/16U2_16MHZ_XTAL1") (class "Default")
      (node (ref "C9") (pin "2") (pinfunction "2_2") (pintype "passive"))
      (node (ref "R10") (pin "2") (pinfunction "2_2") (pintype "passive"))
      (node (ref "U1") (pin "1") (pinfunction "XTAL1_1") (pintype "passive"))
      (node (ref "Y1") (pin "2") (pinfunction "2_2") (pintype "passive"))
    )
    (net (code "10") (name "/16U2_16MHZ_XTAL2") (class "Default")
      (node (ref "C10") (pin "2") (pinfunction "2_2") (pintype "passive"))
      (node (ref "R10") (pin "1") (pinfunction "1_1") (pintype "passive"))
      (node (ref "U1") (pin "2") (pinfunction "(PC0)_XTAL2_2") (pintype "passive"))
      (node (ref "Y1") (pin "1") (pinfunction "1_1") (pintype "passive"))
    )
    (net (code "11") (name "/16U2_BUFF_RESETn") (class "Default")
      (node (ref "C33") (pin "2") (pinfunction "2_2") (pintype "passive"))
      (node (ref "J4") (pin "4") (pinfunction "4_4") (pintype "passive"))
      (node (ref "R28") (pin "2") (pinfunction "2_2") (pintype "passive"))
      (node (ref "U7") (pin "1") (pinfunction "1_1") (pintype "input"))
      (node (ref "U7") (pin "2") (pinfunction "2_2") (pintype "input"))
    )
    (net (code "12") (name "/16U2_HDR_RESETn") (class "Default")
      (node (ref "J2") (pin "5") (pinfunction "5_5") (pintype "passive"))
      (node (ref "J4") (pin "3") (pinfunction "3_3") (pintype "passive"))
    )
    (net (code "13") (name "/16U2_MISO") (class "Default")
      (node (ref "J2") (pin "1") (pinfunction "1_1") (pintype "passive"))
      (node (ref "U1") (pin "17") (pinfunction "PB3_(PDO_/_MISO_/_PCINT3)_17") (pintype "passive"))
    )
    (net (code "14") (name "/16U2_MOSI") (class "Default")
      (node (ref "J2") (pin "4") (pinfunction "4_4") (pintype "passive"))
      (node (ref "U1") (pin "16") (pinfunction "(PDI_/_MOSI_/_PCINT2)_PB2_16") (pintype "passive"))
    )
    (net (code "15") (name "/16U2_PB4") (class "Default")
      (node (ref "J1") (pin "1") (pinfunction "1_1") (pintype "passive"))
      (node (ref "J4") (pin "2") (pinfunction "2_2") (pintype "passive"))
      (node (ref "U1") (pin "18") (pinfunction "PB4_(T1_/_PCINT4)_18") (pintype "passive"))
    )
    (net (code "16") (name "/16U2_PB5") (class "Default")
      (node (ref "J1") (pin "3") (pinfunction "3_3") (pintype "passive"))
      (node (ref "U1") (pin "19") (pinfunction "PB5_(PCINT5)_19") (pintype "passive"))
    )
    (net (code "17") (name "/16U2_PB6") (class "Default")
      (node (ref "J1") (pin "2") (pinfunction "2_2") (pintype "passive"))
      (node (ref "U1") (pin "20") (pinfunction "PB6_(PCINT6)_20") (pintype "passive"))
    )
    (net (code "18") (name "/16U2_PB7") (class "Default")
      (node (ref "J1") (pin "4") (pinfunction "4_4") (pintype "passive"))
      (node (ref "U1") (pin "21") (pinfunction "PB7_(PCINT7_/_OC.0A_/_OC.1C)_21") (pintype "passive"))
    )
    (net (code "19") (name "/16U2_PROG_32P_RESETn") (class "Default")
      (node (ref "J5") (pin "2") (pinfunction "2_2") (pintype "passive"))
      (node (ref "R1") (pin "1") (pinfunction "1_1") (pintype "passive"))
      (node (ref "U1") (pin "13") (pinfunction "~{(HWB}_/_AIN6_/_T0_/_INT7)_PD7_13") (pintype "passive"))
    )
    (net (code "20") (name "/16U2_RESETn") (class "Default")
      (node (ref "R5") (pin "2") (pinfunction "2_2") (pintype "passive"))
      (node (ref "U1") (pin "24") (pinfunction "~{Reset}_(PC1_/_dW)_24") (pintype "passive"))
      (node (ref "U7") (pin "4") (pinfunction "4_4") (pintype "output"))
    )
    (net (code "21") (name "/16U2_RXD") (class "Default")
      (node (ref "R12") (pin "1") (pinfunction "1_1") (pintype "passive"))
      (node (ref "U1") (pin "8") (pinfunction "(RXD1_/_AIN1_/_INT2)_PD2_8") (pintype "passive"))
    )
    (net (code "22") (name "/16U2_RX_LED") (class "Default")
      (node (ref "D2") (pin "1") (pinfunction "Cathode_1") (pintype "passive"))
      (node (ref "U1") (pin "10") (pinfunction "(INT5/_AIN3)_PD4_10") (pintype "passive"))
    )
    (net (code "23") (name "/16U2_SCLK") (class "Default")
      (node (ref "J2") (pin "3") (pinfunction "3_3") (pintype "passive"))
      (node (ref "R6") (pin "2") (pinfunction "2_2") (pintype "passive"))
    )
    (net (code "24") (name "/16U2_SCLK_R") (class "Default")
      (node (ref "R6") (pin "1") (pinfunction "1_1") (pintype "passive"))
      (node (ref "U1") (pin "15") (pinfunction "(SCLK_/_PCINT1)_PB1_15") (pintype "passive"))
    )
    (net (code "25") (name "/16U2_TXD") (class "Default")
      (node (ref "R11") (pin "1") (pinfunction "1_1") (pintype "passive"))
      (node (ref "U1") (pin "9") (pinfunction "(TXD1_/_INT3)_PD3_9") (pintype "passive"))
    )
    (net (code "26") (name "/16U2_TX_LED") (class "Default")
      (node (ref "D1") (pin "1") (pinfunction "Cathode_1") (pintype "passive"))
      (node (ref "U1") (pin "11") (pinfunction "(XCK_AIN4_/_PCINT12)_PD5_11") (pintype "passive"))
    )
    (net (code "27") (name "/328P_16MHZ_XTAL1") (class "Default")
      (node (ref "C25") (pin "2") (pinfunction "2_2") (pintype "passive"))
      (node (ref "R18") (pin "2") (pinfunction "2_2") (pintype "passive"))
      (node (ref "U3") (pin "9") (pinfunction "(PCINT6/XTAL1/TOSC1)_PB6_9") (pintype "passive"))
      (node (ref "Y2") (pin "2") (pinfunction "2_2") (pintype "passive"))
    )
    (net (code "28") (name "/328P_16MHZ_XTAL2") (class "Default")
      (node (ref "C26") (pin "2") (pinfunction "2_2") (pintype "passive"))
      (node (ref "R18") (pin "1") (pinfunction "1_1") (pintype "passive"))
      (node (ref "U3") (pin "10") (pinfunction "(PCINT7/XTAL2/TOSC2)_PB7_10") (pintype "passive"))
      (node (ref "Y2") (pin "1") (pinfunction "1_1") (pintype "passive"))
    )
    (net (code "29") (name "/328P_Auto_RESETn") (class "Default")
      (node (ref "C11") (pin "1") (pinfunction "1_1") (pintype "passive"))
      (node (ref "R21") (pin "1") (pinfunction "1_1") (pintype "passive"))
      (node (ref "U5") (pin "1") (pinfunction "1_1") (pintype "input"))
    )
    (net (code "30") (name "/328P_BUFF_RESETn") (class "Default")
      (node (ref "C31") (pin "2") (pinfunction "2_2") (pintype "passive"))
      (node (ref "R26") (pin "2") (pinfunction "2_2") (pintype "passive"))
      (node (ref "U5") (pin "2") (pinfunction "2_2") (pintype "input"))
    )
    (net (code "31") (name "/328P_RESETn") (class "Default")
      (node (ref "J12") (pin "3") (pinfunction "3_3") (pintype "passive"))
      (node (ref "J4") (pin "1") (pinfunction "1_1") (pintype "passive"))
      (node (ref "J6") (pin "5") (pinfunction "5_5") (pintype "passive"))
      (node (ref "R17") (pin "1") (pinfunction "1_1") (pintype "passive"))
      (node (ref "U3") (pin "1") (pinfunction "(PCINT14/PC6)~{_RESET}_1") (pintype "passive"))
      (node (ref "U5") (pin "4") (pinfunction "4_4") (pintype "output"))
    )
    (net (code "32") (name "/AD0") (class "Default")
      (node (ref "J13") (pin "1") (pinfunction "1_1") (pintype "passive"))
      (node (ref "U3") (pin "23") (pinfunction "PC0_(ADC0/PCINT8)_23") (pintype "passive"))
    )
    (net (code "33") (name "/AD1") (class "Default")
      (node (ref "J13") (pin "2") (pinfunction "2_2") (pintype "passive"))
      (node (ref "U3") (pin "24") (pinfunction "PC1_(ADC1/PCINT9)_24") (pintype "passive"))
    )
    (net (code "34") (name "/AD2") (class "Default")
      (node (ref "J13") (pin "3") (pinfunction "3_3") (pintype "passive"))
      (node (ref "U3") (pin "25") (pinfunction "PC2_(ADC2/PCINT10)_25") (pintype "passive"))
    )
    (net (code "35") (name "/AD3") (class "Default")
      (node (ref "J13") (pin "4") (pinfunction "4_4") (pintype "passive"))
      (node (ref "U3") (pin "26") (pinfunction "PC3_(ADC3/PCINT11)_26") (pintype "passive"))
    )
    (net (code "36") (name "/AD4{slash}SDA") (class "Default")
      (node (ref "J10") (pin "9") (pinfunction "9_9") (pintype "passive"))
      (node (ref "J13") (pin "5") (pinfunction "5_5") (pintype "passive"))
      (node (ref "U3") (pin "27") (pinfunction "PC4_(ADC4/SDA/PCINT12)_27") (pintype "passive"))
    )
    (net (code "37") (name "/AD5{slash}SCI") (class "Default")
      (node (ref "J10") (pin "10") (pinfunction "10_10") (pintype "passive"))
      (node (ref "J13") (pin "6") (pinfunction "6_6") (pintype "passive"))
      (node (ref "U3") (pin "28") (pinfunction "PC5_(ADC5/SCL/PCINT13)_28") (pintype "passive"))
    )
    (net (code "38") (name "/BUTTON_RESETn") (class "Default")
      (node (ref "D5") (pin "2") (pinfunction "Anode_2") (pintype "passive"))
      (node (ref "R22") (pin "1") (pinfunction "1_1") (pintype "passive"))
      (node (ref "R26") (pin "1") (pinfunction "1_1") (pintype "passive"))
      (node (ref "SW1") (pin "1") (pinfunction "1_1") (pintype "passive"))
      (node (ref "SW1") (pin "2") (pinfunction "2_2") (pintype "passive"))
    )
    (net (code "39") (name "/CON_USB_N") (class "Default")
      (node (ref "J3") (pin "2") (pinfunction "2_2") (pintype "passive"))
      (node (ref "R7") (pin "1") (pinfunction "1_1") (pintype "passive"))
      (node (ref "Z1") (pin "1") (pinfunction "1_1") (pintype "passive"))
    )
    (net (code "40") (name "/CON_USB_P") (class "Default")
      (node (ref "J3") (pin "3") (pinfunction "3_3") (pintype "passive"))
      (node (ref "R8") (pin "1") (pinfunction "1_1") (pintype "passive"))
      (node (ref "Z2") (pin "1") (pinfunction "1_1") (pintype "passive"))
    )
    (net (code "41") (name "/IO1") (class "Default")
      (node (ref "J14") (pin "1") (pinfunction "1_1") (pintype "passive"))
      (node (ref "R11") (pin "2") (pinfunction "2_2") (pintype "passive"))
      (node (ref "U3") (pin "2") (pinfunction "(PCINT16/RXD)_PD0_2") (pintype "passive"))
    )
    (net (code "42") (name "/IO2") (class "Default")
      (node (ref "J14") (pin "2") (pinfunction "2_2") (pintype "passive"))
      (node (ref "R12") (pin "2") (pinfunction "2_2") (pintype "passive"))
      (node (ref "U3") (pin "3") (pinfunction "(PCINT17/TXD)_PD1_3") (pintype "passive"))
    )
    (net (code "43") (name "/IO3") (class "Default")
      (node (ref "J14") (pin "3") (pinfunction "3_3") (pintype "passive"))
      (node (ref "U3") (pin "4") (pinfunction "(PCINT18/INT0)_PD2_4") (pintype "passive"))
    )
    (net (code "44") (name "/IO4") (class "Default")
      (node (ref "J14") (pin "4") (pinfunction "4_4") (pintype "passive"))
      (node (ref "U3") (pin "5") (pinfunction "(PCINT19/OC2B/INT1)_PD3_5") (pintype "passive"))
    )
    (net (code "45") (name "/IO5") (class "Default")
      (node (ref "J14") (pin "5") (pinfunction "5_5") (pintype "passive"))
      (node (ref "U3") (pin "6") (pinfunction "(PCINT20/XCK/T0)_PD4_6") (pintype "passive"))
    )
    (net (code "46") (name "/IO6") (class "Default")
      (node (ref "J14") (pin "6") (pinfunction "6_6") (pintype "passive"))
      (node (ref "U3") (pin "11") (pinfunction "(PCINT21/OC0B/T1)_PD5_11") (pintype "passive"))
    )
    (net (code "47") (name "/IO7") (class "Default")
      (node (ref "J14") (pin "7") (pinfunction "7_7") (pintype "passive"))
      (node (ref "U3") (pin "12") (pinfunction "(PCINT22/OC0A/AIN0)_PD6_12") (pintype "passive"))
    )
    (net (code "48") (name "/IO8") (class "Default")
      (node (ref "J14") (pin "8") (pinfunction "8_8") (pintype "passive"))
      (node (ref "U3") (pin "13") (pinfunction "(PCINT23/AIN1)_PD7_13") (pintype "passive"))
    )
    (net (code "49") (name "/IO9") (class "Default")
      (node (ref "J10") (pin "1") (pinfunction "1_1") (pintype "passive"))
      (node (ref "R25") (pin "2") (pinfunction "2_2") (pintype "passive"))
      (node (ref "U3") (pin "14") (pinfunction "(PCINT0/CLKO/ICP1)_PB0_14") (pintype "passive"))
    )
    (net (code "50") (name "/IO10") (class "Default")
      (node (ref "J10") (pin "2") (pinfunction "2_2") (pintype "passive"))
      (node (ref "U3") (pin "15") (pinfunction "PB1_(OC1A/PCINT1)_15") (pintype "passive"))
    )
    (net (code "51") (name "/MISO") (class "Default")
      (node (ref "J10") (pin "5") (pinfunction "5_5") (pintype "passive"))
      (node (ref "J6") (pin "1") (pinfunction "1_1") (pintype "passive"))
      (node (ref "U3") (pin "18") (pinfunction "PB4_(MISO/PCINT4)_18") (pintype "passive"))
    )
    (net (code "52") (name "/MOSI") (class "Default")
      (node (ref "J10") (pin "4") (pinfunction "4_4") (pintype "passive"))
      (node (ref "J6") (pin "4") (pinfunction "4_4") (pintype "passive"))
      (node (ref "U3") (pin "17") (pinfunction "PB3_(MOSI/OC2A/PCINT3)_17") (pintype "passive"))
    )
    (net (code "53") (name "/SCK") (class "Default")
      (node (ref "J10") (pin "6") (pinfunction "6_6") (pintype "passive"))
      (node (ref "J6") (pin "3") (pinfunction "3_3") (pintype "passive"))
      (node (ref "R16") (pin "2") (pinfunction "2_2") (pintype "passive"))
      (node (ref "U4") (pin "1") (pinfunction "1_1") (pintype "input"))
      (node (ref "U4") (pin "2") (pinfunction "2_2") (pintype "input"))
    )
    (net (code "54") (name "/SCK_R") (class "Default")
      (node (ref "R16") (pin "1") (pinfunction "1_1") (pintype "passive"))
      (node (ref "U3") (pin "19") (pinfunction "PB5_(SCK/PCINT5)_19") (pintype "passive"))
    )
    (net (code "55") (name "/SS") (class "Default")
      (node (ref "J10") (pin "3") (pinfunction "3_3") (pintype "passive"))
      (node (ref "U3") (pin "16") (pinfunction "PB2_(SS/OC1B/PCINT2)_16") (pintype "passive"))
    )
    (net (code "56") (name "/USB_N") (class "Default")
      (node (ref "R7") (pin "2") (pinfunction "2_2") (pintype "passive"))
      (node (ref "U1") (pin "30") (pinfunction "D-_30") (pintype "passive"))
    )
    (net (code "57") (name "/USB_P") (class "Default")
      (node (ref "R8") (pin "2") (pinfunction "2_2") (pintype "passive"))
      (node (ref "U1") (pin "29") (pinfunction "D+_29") (pintype "passive"))
    )
    (net (code "58") (name "/USER_BUTTON") (class "Default")
      (node (ref "R23") (pin "1") (pinfunction "1_1") (pintype "passive"))
      (node (ref "R27") (pin "1") (pinfunction "1_1") (pintype "passive"))
      (node (ref "SW2") (pin "1") (pinfunction "1_1") (pintype "passive"))
      (node (ref "SW2") (pin "2") (pinfunction "2_2") (pintype "passive"))
    )
    (net (code "59") (name "/USER_BUTTON_BUFF") (class "Default")
      (node (ref "C32") (pin "2") (pinfunction "2_2") (pintype "passive"))
      (node (ref "R27") (pin "2") (pinfunction "2_2") (pintype "passive"))
      (node (ref "U6") (pin "1") (pinfunction "1_1") (pintype "input"))
      (node (ref "U6") (pin "2") (pinfunction "2_2") (pintype "input"))
    )
    (net (code "60") (name "GND") (class "Default")
      (node (ref "C1") (pin "1") (pinfunction "1_1") (pintype "passive"))
      (node (ref "C10") (pin "1") (pinfunction "1_1") (pintype "passive"))
      (node (ref "C12") (pin "1") (pinfunction "1_1") (pintype "passive"))
      (node (ref "C13") (pin "1") (pinfunction "1_1") (pintype "passive"))
      (node (ref "C14") (pin "1") (pinfunction "1_1") (pintype "passive"))
      (node (ref "C15") (pin "1") (pinfunction "1_1") (pintype "passive"))
      (node (ref "C16") (pin "1") (pinfunction "1_1") (pintype "passive"))
      (node (ref "C17") (pin "1") (pinfunction "1_1") (pintype "passive"))
      (node (ref "C18") (pin "1") (pinfunction "1_1") (pintype "passive"))
      (node (ref "C19") (pin "1") (pinfunction "1_1") (pintype "passive"))
      (node (ref "C2") (pin "1") (pinfunction "1_1") (pintype "passive"))
      (node (ref "C20") (pin "1") (pinfunction "1_1") (pintype "passive"))
      (node (ref "C21") (pin "1") (pinfunction "1_1") (pintype "passive"))
      (node (ref "C22") (pin "1") (pinfunction "1_1") (pintype "passive"))
      (node (ref "C23") (pin "1") (pinfunction "1_1") (pintype "passive"))
      (node (ref "C24") (pin "1") (pinfunction "1_1") (pintype "passive"))
      (node (ref "C25") (pin "1") (pinfunction "1_1") (pintype "passive"))
      (node (ref "C26") (pin "1") (pinfunction "1_1") (pintype "passive"))
      (node (ref "C27") (pin "1") (pinfunction "1_1") (pintype "passive"))
      (node (ref "C28") (pin "1") (pinfunction "1_1") (pintype "passive"))
      (node (ref "C29") (pin "1") (pinfunction "1_1") (pintype "passive"))
      (node (ref "C3") (pin "1") (pinfunction "1_1") (pintype "passive"))
      (node (ref "C30") (pin "1") (pinfunction "1_1") (pintype "passive"))
      (node (ref "C31") (pin "1") (pinfunction "1_1") (pintype "passive"))
      (node (ref "C32") (pin "1") (pinfunction "1_1") (pintype "passive"))
      (node (ref "C33") (pin "1") (pinfunction "1_1") (pintype "passive"))
      (node (ref "C4") (pin "2") (pinfunction "2_2") (pintype "passive"))
      (node (ref "C5") (pin "2") (pinfunction "2_2") (pintype "passive"))
      (node (ref "C6") (pin "1") (pinfunction "1_1") (pintype "passive"))
      (node (ref "C7") (pin "1") (pinfunction "1_1") (pintype "passive"))
      (node (ref "C8") (pin "1") (pinfunction "1_1") (pintype "passive"))
      (node (ref "C9") (pin "1") (pinfunction "1_1") (pintype "passive"))
      (node (ref "J10") (pin "7") (pinfunction "7_7") (pintype "passive"))
      (node (ref "J11") (pin "1") (pintype "passive"))
      (node (ref "J12") (pin "6") (pinfunction "6_6") (pintype "passive"))
      (node (ref "J12") (pin "7") (pinfunction "7_7") (pintype "passive"))
      (node (ref "J2") (pin "6") (pinfunction "6_6") (pintype "passive"))
      (node (ref "J3") (pin "10") (pinfunction "10_10") (pintype "passive"))
      (node (ref "J3") (pin "11") (pinfunction "11_11") (pintype "passive"))
      (node (ref "J3") (pin "5") (pinfunction "5_5") (pintype "passive"))
      (node (ref "J3") (pin "6") (pinfunction "6_6") (pintype "passive"))
      (node (ref "J3") (pin "7") (pinfunction "7_7") (pintype "passive"))
      (node (ref "J3") (pin "8") (pinfunction "8_8") (pintype "passive"))
      (node (ref "J3") (pin "9") (pinfunction "9_9") (pintype "passive"))
      (node (ref "J6") (pin "6") (pinfunction "6_6") (pintype "passive"))
      (node (ref "MH1") (pin "1") (pintype "passive"))
      (node (ref "MH2") (pin "1") (pintype "passive"))
      (node (ref "MH3") (pin "1") (pintype "passive"))
      (node (ref "R13") (pin "1") (pinfunction "1_1") (pintype "passive"))
      (node (ref "R20") (pin "1") (pinfunction "1_1") (pintype "passive"))
      (node (ref "R9") (pin "2") (pinfunction "2_2") (pintype "passive"))
      (node (ref "SW1") (pin "3") (pinfunction "3_3") (pintype "passive"))
      (node (ref "SW1") (pin "4") (pinfunction "4_4") (pintype "passive"))
      (node (ref "SW2") (pin "3") (pinfunction "3_3") (pintype "passive"))
      (node (ref "SW2") (pin "4") (pinfunction "4_4") (pintype "passive"))
      (node (ref "U1") (pin "28") (pinfunction "UGND_28") (pintype "passive"))
      (node (ref "U1") (pin "3") (pinfunction "GND_3") (pintype "passive"))
      (node (ref "U2") (pin "3") (pinfunction "GND_3") (pintype "passive"))
      (node (ref "U2") (pin "6") (pinfunction "EPAD_6") (pintype "passive"))
      (node (ref "U3") (pin "22") (pinfunction "GND_2_22") (pintype "passive"))
      (node (ref "U3") (pin "8") (pinfunction "GND_1_8") (pintype "passive"))
      (node (ref "U4") (pin "3") (pinfunction "3_3") (pintype "passive"))
      (node (ref "U5") (pin "3") (pinfunction "3_3") (pintype "passive"))
      (node (ref "U6") (pin "3") (pinfunction "3_3") (pintype "passive"))
      (node (ref "U7") (pin "3") (pinfunction "3_3") (pintype "passive"))
      (node (ref "Z1") (pin "2") (pinfunction "2_2") (pintype "passive"))
      (node (ref "Z2") (pin "2") (pinfunction "2_2") (pintype "passive"))
    )
    (net (code "61") (name "Net-(C11-Pad2)") (class "Default")
      (node (ref "C11") (pin "2") (pinfunction "2_2") (pintype "passive"))
      (node (ref "J5") (pin "1") (pinfunction "1_1") (pintype "passive"))
    )
    (net (code "62") (name "Net-(D1-Anode)") (class "Default")
      (node (ref "D1") (pin "2") (pinfunction "Anode_2") (pintype "passive"))
      (node (ref "R2") (pin "1") (pinfunction "1_1") (pintype "passive"))
    )
    (net (code "63") (name "Net-(D2-Anode)") (class "Default")
      (node (ref "D2") (pin "2") (pinfunction "Anode_2") (pintype "passive"))
      (node (ref "R3") (pin "1") (pinfunction "1_1") (pintype "passive"))
    )
    (net (code "64") (name "Net-(D3-Cathode)") (class "Default")
      (node (ref "D3") (pin "1") (pinfunction "Cathode_1") (pintype "passive"))
      (node (ref "R19") (pin "2") (pinfunction "2_2") (pintype "passive"))
    )
    (net (code "65") (name "Net-(D4-Cathode)") (class "Default")
      (node (ref "D4") (pin "1") (pinfunction "Cathode_1") (pintype "passive"))
      (node (ref "R20") (pin "2") (pinfunction "2_2") (pintype "passive"))
    )
    (net (code "66") (name "Net-(D6-Anode)") (class "Default")
      (node (ref "D6") (pin "2") (pinfunction "Anode_2") (pintype "passive"))
      (node (ref "R24") (pin "1") (pinfunction "1_1") (pintype "passive"))
      (node (ref "R28") (pin "1") (pinfunction "1_1") (pintype "passive"))
    )
    (net (code "67") (name "Net-(J3-Pad4)") (class "Default")
      (node (ref "J3") (pin "4") (pinfunction "4_4") (pintype "passive"))
      (node (ref "R9") (pin "1") (pinfunction "1_1") (pintype "passive"))
    )
    (net (code "68") (name "Net-(J5-Pad3)") (class "Default")
      (node (ref "J5") (pin "3") (pinfunction "3_3") (pintype "passive"))
      (node (ref "R13") (pin "2") (pinfunction "2_2") (pintype "passive"))
    )
    (net (code "69") (name "Net-(R19-Pad1)") (class "Default")
      (node (ref "R19") (pin "1") (pinfunction "1_1") (pintype "passive"))
      (node (ref "U4") (pin "4") (pinfunction "4_4") (pintype "output"))
    )
    (net (code "70") (name "Net-(R25-Pad1)") (class "Default")
      (node (ref "R25") (pin "1") (pinfunction "1_1") (pintype "passive"))
      (node (ref "U6") (pin "4") (pinfunction "4_4") (pintype "output"))
    )
    (net (code "71") (name "Net-(U3-AVCC)") (class "Default")
      (node (ref "C22") (pin "2") (pinfunction "2_2") (pintype "passive"))
      (node (ref "C23") (pin "2") (pinfunction "2_2") (pintype "passive"))
      (node (ref "FB3") (pin "2") (pinfunction "2_2") (pintype "passive"))
      (node (ref "U3") (pin "20") (pinfunction "AVCC_20") (pintype "passive"))
    )
    (net (code "72") (name "unconnected-(J7-Pad1)") (class "Default")
      (node (ref "J7") (pin "1") (pintype "passive+no_connect"))
    )
    (net (code "73") (name "unconnected-(J12-Pad1)") (class "Default")
      (node (ref "J12") (pin "1") (pinfunction "1_1") (pintype "passive+no_connect"))
    )
    (net (code "74") (name "unconnected-(J12-Pad8)") (class "Default")
      (node (ref "J12") (pin "8") (pinfunction "8_8") (pintype "passive+no_connect"))
    )
    (net (code "75") (name "unconnected-(U1-(AIN0_{slash}_INT1)_PD1-Pad7)") (class "Default")
      (node (ref "U1") (pin "7") (pinfunction "(AIN0_/_INT1)_PD1_7") (pintype "passive+no_connect"))
    )
    (net (code "76") (name "unconnected-(U1-(OC.0B_{slash}_INT0)_PD0-Pad6)") (class "Default")
      (node (ref "U1") (pin "6") (pinfunction "(OC.0B_/_INT0)_PD0_6") (pintype "passive+no_connect"))
    )
    (net (code "77") (name "unconnected-(U1-(PCINT11_{slash}AIN2_)_PC2-Pad5)") (class "Default")
      (node (ref "U1") (pin "5") (pinfunction "(PCINT11_/AIN2_)_PC2_5") (pintype "passive+no_connect"))
    )
    (net (code "78") (name "unconnected-(U1-PC4_(PCINT10)-Pad26)") (class "Default")
      (node (ref "U1") (pin "26") (pinfunction "PC4_(PCINT10)_26") (pintype "passive+no_connect"))
    )
    (net (code "79") (name "unconnected-(U1-PC5_(_PCINT9{slash}_OC.1B)-Pad25)") (class "Default")
      (node (ref "U1") (pin "25") (pinfunction "PC5_(_PCINT9/_OC.1B)_25") (pintype "passive+no_connect"))
    )
    (net (code "80") (name "unconnected-(U1-PC6_(OC.1A_{slash}_PCINT8)-Pad23)") (class "Default")
      (node (ref "U1") (pin "23") (pinfunction "PC6_(OC.1A_/_PCINT8)_23") (pintype "passive+no_connect"))
    )
    (net (code "81") (name "unconnected-(U1-PC7_(INT4_{slash}_ICP1_{slash}_CLKO)-Pad22)") (class "Default")
      (node (ref "U1") (pin "22") (pinfunction "PC7_(INT4_/_ICP1_/_CLKO)_22") (pintype "passive+no_connect"))
    )
    (net (code "82") (name "unconnected-(U1-~{(RTS}_{slash}_AIN5_{slash}_INT6)_PD6-Pad12)") (class "Default")
      (node (ref "U1") (pin "12") (pinfunction "~{(RTS}_/_AIN5_/_INT6)_PD6_12") (pintype "passive+no_connect"))
    )
    (net (code "83") (name "unconnected-(U1-~{(SS}_{slash}_PCINT0)_PB0-Pad14)") (class "Default")
      (node (ref "U1") (pin "14") (pinfunction "~{(SS}_/_PCINT0)_PB0_14") (pintype "passive+no_connect"))
    )
  )
)
